# out_drv.net
KiCad netlist of a schematic drawn in Altium Designer
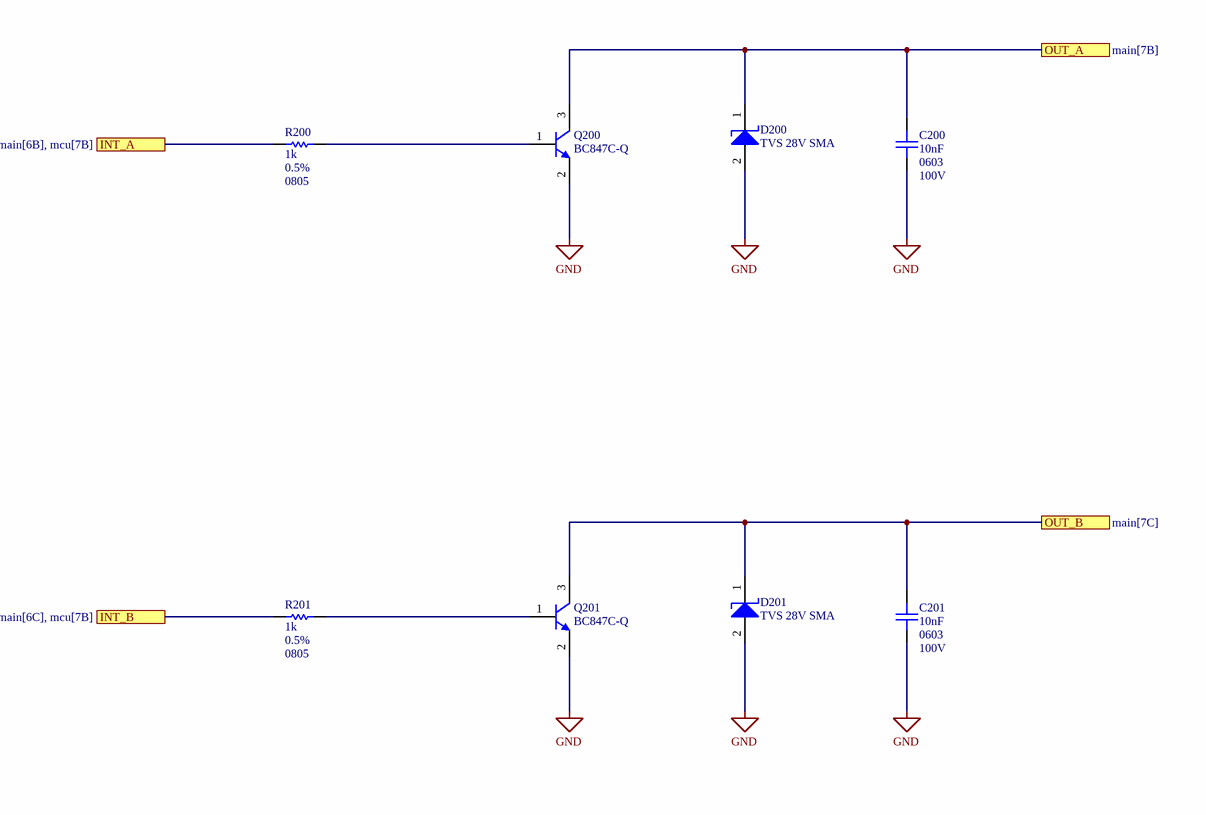
[diagram p0: out_drv.SchDoc, left]

(export (version "E")
  (design (tool "Eeschema 10.0.6"))
  (components
    (comp (ref "C200")
      (value "10nF")
      (footprint "CER0603")
      (description "MLCC Automotive, 10nF, 0603, 100V, 10%, X7R")
      (fields
        (field (name "CASE/PACKAGE") "0603")
        (field (name "OP VOLTAGE") "100V")
        (field (name "TOLERANCE") "10%")
      )
      (libsource (lib "PMP_CapsDB") (part "CapCer_SMD_2"))
    )
    (comp (ref "C201")
      (value "10nF")
      (footprint "CER0603")
      (description "MLCC Automotive, 10nF, 0603, 100V, 10%, X7R")
      (fields
        (field (name "CASE/PACKAGE") "0603")
        (field (name "OP VOLTAGE") "100V")
        (field (name "TOLERANCE") "10%")
      )
      (libsource (lib "PMP_CapsDB") (part "CapCer_SMD_2"))
    )
    (comp (ref "D200")
      (value "TVS 28V SMA")
      (footprint "DO-214AC_SMA")
      (description "TVS Uniir 28V SMA")
      (fields (field (name "Comment") "SMD/PTH TVS Unidirectional Diode"))
      (libsource (lib "Pmp_DiscretesDB") (part "TVS_2_Unidirectional"))
    )
    (comp (ref "D201")
      (value "TVS 28V SMA")
      (footprint "DO-214AC_SMA")
      (description "TVS Uniir 28V SMA")
      (fields (field (name "Comment") "SMD/PTH TVS Unidirectional Diode"))
      (libsource (lib "Pmp_DiscretesDB") (part "TVS_2_Unidirectional"))
    )
    (comp (ref "Q200")
      (value "BC847C-Q")
      (footprint "SOT95P230X110-3N")
      (description "NPN general purpose transistors")
      (fields (field (name "Comment") "NPN Transistor SMD"))
      (libsource (lib "Pmp_DiscretesDB") (part "TRANS_SMD_3_NPN_BEC"))
    )
    (comp (ref "Q201")
      (value "BC847C-Q")
      (footprint "SOT95P230X110-3N")
      (description "NPN general purpose transistors")
      (fields (field (name "Comment") "NPN Transistor SMD"))
      (libsource (lib "Pmp_DiscretesDB") (part "TRANS_SMD_3_NPN_BEC"))
    )
    (comp (ref "R200")
      (value "1k")
      (footprint "Res0603")
      (description "Thick Film SM Chip Resistors, 1K, 0805, ±0.5%, 1/2W")
      (fields
        (field (name "TOLERANCE") "0.5%")
        (field (name "CASE/PACKAGE") "0805")
        (field (name "POWER") "500mW")
        (field (name "Comment") "SMD Resistor")
      )
      (libsource (lib "PMP_ResDB") (part "Res_SMD_2"))
    )
    (comp (ref "R201")
      (value "1k")
      (footprint "Res0603")
      (description "Thick Film SM Chip Resistors, 1K, 0805, ±0.5%, 1/2W")
      (fields
        (field (name "TOLERANCE") "0.5%")
        (field (name "CASE/PACKAGE") "0805")
        (field (name "POWER") "500mW")
        (field (name "Comment") "SMD Resistor")
      )
      (libsource (lib "PMP_ResDB") (part "Res_SMD_2"))
    )
  )
  (nets
    (net (code "1") (name "/INT_A") (class "Default")
      (node (ref "R200") (pin "1") (pinfunction "1_1") (pintype "passive"))
    )
    (net (code "2") (name "/INT_B") (class "Default")
      (node (ref "R201") (pin "1") (pinfunction "1_1") (pintype "passive"))
    )
    (net (code "3") (name "/OUT_A") (class "Default")
      (node (ref "C200") (pin "1") (pinfunction "1_1") (pintype "passive"))
      (node (ref "D200") (pin "1") (pinfunction "K_1") (pintype "passive"))
      (node (ref "Q200") (pin "3") (pinfunction "C_3") (pintype "passive"))
    )
    (net (code "4") (name "/OUT_B") (class "Default")
      (node (ref "C201") (pin "1") (pinfunction "1_1") (pintype "passive"))
      (node (ref "D201") (pin "1") (pinfunction "K_1") (pintype "passive"))
      (node (ref "Q201") (pin "3") (pinfunction "C_3") (pintype "passive"))
    )
    (net (code "5") (name "GND") (class "Default")
      (node (ref "C200") (pin "2") (pinfunction "2_2") (pintype "passive"))
      (node (ref "C201") (pin "2") (pinfunction "2_2") (pintype "passive"))
      (node (ref "D200") (pin "2") (pinfunction "A_2") (pintype "passive"))
      (node (ref "D201") (pin "2") (pinfunction "A_2") (pintype "passive"))
      (node (ref "Q200") (pin "2") (pinfunction "E_2") (pintype "passive"))
      (node (ref "Q201") (pin "2") (pinfunction "E_2") (pintype "passive"))
    )
    (net (code "6") (name "Net-(Q200-B)") (class "Default")
      (node (ref "Q200") (pin "1") (pinfunction "B_1") (pintype "passive"))
      (node (ref "R200") (pin "2") (pinfunction "2_2") (pintype "passive"))
    )
    (net (code "7") (name "Net-(Q201-B)") (class "Default")
      (node (ref "Q201") (pin "1") (pinfunction "B_1") (pintype "passive"))
      (node (ref "R201") (pin "2") (pinfunction "2_2") (pintype "passive"))
    )
  )
)
